# USB-PS2.net
KiCad netlist of a schematic drawn in EAGLE
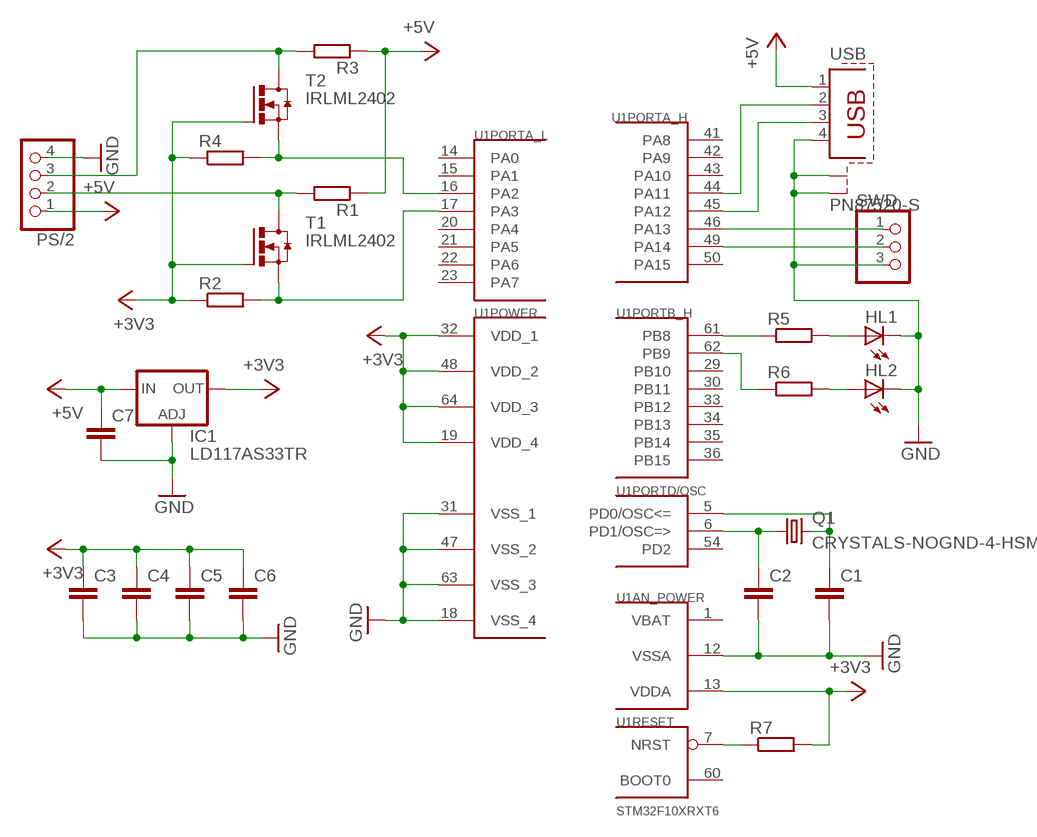
[diagram p0: schematic, sheet 1]

(export (version "E")
  (design (tool "Eeschema 10.0.6"))
  (components
    (comp (ref "C1")
      (value "C-EUC0603K")
      (footprint "eagle-import:C0603K")
      (libsource (lib "eagle-import") (part "C-EUC0603K"))
    )
    (comp (ref "C2")
      (value "C-EUC0603K")
      (footprint "eagle-import:C0603K")
      (libsource (lib "eagle-import") (part "C-EUC0603K"))
    )
    (comp (ref "C3")
      (value "C-EUC0603K")
      (footprint "eagle-import:C0603K")
      (libsource (lib "eagle-import") (part "C-EUC0603K"))
    )
    (comp (ref "C4")
      (value "C-EUC0603K")
      (footprint "eagle-import:C0603K")
      (libsource (lib "eagle-import") (part "C-EUC0603K"))
    )
    (comp (ref "C5")
      (value "C-EUC0603K")
      (footprint "eagle-import:C0603K")
      (libsource (lib "eagle-import") (part "C-EUC0603K"))
    )
    (comp (ref "C6")
      (value "C-EUC0603K")
      (footprint "eagle-import:C0603K")
      (libsource (lib "eagle-import") (part "C-EUC0603K"))
    )
    (comp (ref "C7")
      (value "C-EUC0603K")
      (footprint "eagle-import:C0603K")
      (libsource (lib "eagle-import") (part "C-EUC0603K"))
    )
    (comp (ref "HL1")
      (value "LEDSML0805")
      (footprint "eagle-import:SML0805")
      (libsource (lib "eagle-import") (part "LEDSML0805"))
    )
    (comp (ref "HL2")
      (value "LEDSML0805")
      (footprint "eagle-import:SML0805")
      (libsource (lib "eagle-import") (part "LEDSML0805"))
    )
    (comp (ref "IC1")
      (value "LD117AS33TR")
      (footprint "eagle-import:SOT223")
      (libsource (lib "eagle-import") (part "LD117A?S33TR"))
    )
    (comp (ref "PS/2")
      (value "PINHD-1X4")
      (footprint "eagle-import:1X04")
      (libsource (lib "eagle-import") (part "PINHD-1X4"))
    )
    (comp (ref "Q1")
      (value "CRYSTALS-NOGND-4-HSMX")
      (footprint "eagle-import:HC49-4-HSMX")
      (libsource (lib "eagle-import") (part "CRYSTALS-NOGND-4-HSMX"))
    )
    (comp (ref "R1")
      (value "R-EU_R0603")
      (footprint "eagle-import:R0603")
      (libsource (lib "eagle-import") (part "R-EU_R0603"))
    )
    (comp (ref "R2")
      (value "R-EU_R0603")
      (footprint "eagle-import:R0603")
      (libsource (lib "eagle-import") (part "R-EU_R0603"))
    )
    (comp (ref "R3")
      (value "R-EU_R0603")
      (footprint "eagle-import:R0603")
      (libsource (lib "eagle-import") (part "R-EU_R0603"))
    )
    (comp (ref "R4")
      (value "R-EU_R0603")
      (footprint "eagle-import:R0603")
      (libsource (lib "eagle-import") (part "R-EU_R0603"))
    )
    (comp (ref "R5")
      (value "R-EU_R0603")
      (footprint "eagle-import:R0603")
      (libsource (lib "eagle-import") (part "R-EU_R0603"))
    )
    (comp (ref "R6")
      (value "R-EU_R0603")
      (footprint "eagle-import:R0603")
      (libsource (lib "eagle-import") (part "R-EU_R0603"))
    )
    (comp (ref "R7")
      (value "R-EU_R0603")
      (footprint "eagle-import:R0603")
      (libsource (lib "eagle-import") (part "R-EU_R0603"))
    )
    (comp (ref "SWD")
      (value "PINHD-1X3")
      (footprint "eagle-import:1X03")
      (libsource (lib "eagle-import") (part "PINHD-1X3"))
    )
    (comp (ref "T1")
      (value "IRLML2402")
      (footprint "eagle-import:MICRO3")
      (libsource (lib "eagle-import") (part "IRLML2402"))
    )
    (comp (ref "T2")
      (value "IRLML2402")
      (footprint "eagle-import:MICRO3")
      (libsource (lib "eagle-import") (part "IRLML2402"))
    )
    (comp (ref "U1")
      (value "STM32F10XRXT6")
      (footprint "eagle-import:TQFP64")
      (libsource (lib "eagle-import") (part "STM32F10XRXT6"))
    )
    (comp (ref "USB")
      (value "PN87520-S")
      (footprint "eagle-import:PN87520-S")
      (libsource (lib "eagle-import") (part "PN87520-S"))
    )
  )
  (nets
    (net (code "1") (name "+3V3") (class "Default")
      (node (ref "C3") (pin "1") (pinfunction "1_1") (pintype "passive"))
      (node (ref "C4") (pin "1") (pinfunction "1_1") (pintype "passive"))
      (node (ref "C5") (pin "1") (pinfunction "1_1") (pintype "passive"))
      (node (ref "C6") (pin "1") (pinfunction "1_1") (pintype "passive"))
      (node (ref "IC1") (pin "4") (pinfunction "OUT_4") (pintype "passive"))
      (node (ref "R2") (pin "1") (pinfunction "1_1") (pintype "passive"))
      (node (ref "R4") (pin "1") (pinfunction "1_1") (pintype "passive"))
      (node (ref "R7") (pin "2") (pinfunction "2_2") (pintype "passive"))
      (node (ref "T1") (pin "1") (pinfunction "G_1") (pintype "passive"))
      (node (ref "T2") (pin "1") (pinfunction "G_1") (pintype "passive"))
      (node (ref "U1") (pin "13") (pinfunction "VDDA_13") (pintype "power_in"))
      (node (ref "U1") (pin "19") (pinfunction "VDD_4_19") (pintype "power_in"))
      (node (ref "U1") (pin "32") (pinfunction "VDD_1_32") (pintype "power_in"))
      (node (ref "U1") (pin "48") (pinfunction "VDD_2_48") (pintype "power_in"))
      (node (ref "U1") (pin "64") (pinfunction "VDD_3_64") (pintype "power_in"))
    )
    (net (code "2") (name "+5V") (class "Default")
      (node (ref "C7") (pin "1") (pinfunction "1_1") (pintype "passive"))
      (node (ref "IC1") (pin "3") (pinfunction "IN_3") (pintype "input"))
      (node (ref "PS/2") (pin "1") (pinfunction "1_1") (pintype "passive"))
      (node (ref "R1") (pin "1") (pinfunction "1_1") (pintype "passive"))
      (node (ref "R3") (pin "1") (pinfunction "1_1") (pintype "passive"))
      (node (ref "USB") (pin "1") (pinfunction "1_1") (pintype "passive"))
    )
    (net (code "3") (name "/VBAT") (class "Default")
      (node (ref "U1") (pin "1") (pinfunction "VBAT_1") (pintype "power_in"))
    )
    (net (code "4") (name "GND") (class "Default")
      (node (ref "C1") (pin "2") (pinfunction "2_2") (pintype "passive"))
      (node (ref "C2") (pin "2") (pinfunction "2_2") (pintype "passive"))
      (node (ref "C3") (pin "2") (pinfunction "2_2") (pintype "passive"))
      (node (ref "C4") (pin "2") (pinfunction "2_2") (pintype "passive"))
      (node (ref "C5") (pin "2") (pinfunction "2_2") (pintype "passive"))
      (node (ref "C6") (pin "2") (pinfunction "2_2") (pintype "passive"))
      (node (ref "C7") (pin "2") (pinfunction "2_2") (pintype "passive"))
      (node (ref "HL1") (pin "C") (pinfunction "C_C") (pintype "passive"))
      (node (ref "HL2") (pin "C") (pinfunction "C_C") (pintype "passive"))
      (node (ref "IC1") (pin "1") (pinfunction "ADJ_1") (pintype "input"))
      (node (ref "PS/2") (pin "4") (pinfunction "4_4") (pintype "passive"))
      (node (ref "SWD") (pin "3") (pinfunction "3_3") (pintype "passive"))
      (node (ref "U1") (pin "12") (pinfunction "VSSA_12") (pintype "power_in"))
      (node (ref "U1") (pin "18") (pinfunction "VSS_4_18") (pintype "power_in"))
      (node (ref "U1") (pin "31") (pinfunction "VSS_1_31") (pintype "power_in"))
      (node (ref "U1") (pin "47") (pinfunction "VSS_2_47") (pintype "power_in"))
      (node (ref "U1") (pin "63") (pinfunction "VSS_3_63") (pintype "power_in"))
      (node (ref "USB") (pin "4") (pinfunction "4_4") (pintype "passive"))
      (node (ref "USB") (pin "S1") (pinfunction "S1_S1") (pintype "passive"))
      (node (ref "USB") (pin "S2") (pinfunction "S2_S2") (pintype "passive"))
    )
    (net (code "5") (name "Net-(HL1-PadA)") (class "Default")
      (node (ref "HL1") (pin "A") (pinfunction "A_A") (pintype "passive"))
      (node (ref "R5") (pin "2") (pinfunction "2_2") (pintype "passive"))
    )
    (net (code "6") (name "Net-(HL2-PadA)") (class "Default")
      (node (ref "HL2") (pin "A") (pinfunction "A_A") (pintype "passive"))
      (node (ref "R6") (pin "2") (pinfunction "2_2") (pintype "passive"))
    )
    (net (code "7") (name "Net-(T1-D)") (class "Default")
      (node (ref "PS/2") (pin "2") (pinfunction "2_2") (pintype "passive"))
      (node (ref "R1") (pin "2") (pinfunction "2_2") (pintype "passive"))
      (node (ref "T1") (pin "3") (pinfunction "D_3") (pintype "passive"))
    )
    (net (code "8") (name "Net-(T1-S)") (class "Default")
      (node (ref "R2") (pin "2") (pinfunction "2_2") (pintype "passive"))
      (node (ref "T1") (pin "2") (pinfunction "S_2") (pintype "passive"))
      (node (ref "U1") (pin "17") (pinfunction "PA3_17") (pintype "bidirectional"))
    )
    (net (code "9") (name "Net-(T2-D)") (class "Default")
      (node (ref "PS/2") (pin "3") (pinfunction "3_3") (pintype "passive"))
      (node (ref "R3") (pin "2") (pinfunction "2_2") (pintype "passive"))
      (node (ref "T2") (pin "3") (pinfunction "D_3") (pintype "passive"))
    )
    (net (code "10") (name "Net-(T2-S)") (class "Default")
      (node (ref "R4") (pin "2") (pinfunction "2_2") (pintype "passive"))
      (node (ref "T2") (pin "2") (pinfunction "S_2") (pintype "passive"))
      (node (ref "U1") (pin "16") (pinfunction "PA2_16") (pintype "bidirectional"))
    )
    (net (code "11") (name "Net-(U1B-PA11)") (class "Default")
      (node (ref "U1") (pin "44") (pinfunction "PA11_44") (pintype "bidirectional"))
      (node (ref "USB") (pin "2") (pinfunction "2_2") (pintype "passive"))
    )
    (net (code "12") (name "Net-(U1B-PA12)") (class "Default")
      (node (ref "U1") (pin "45") (pinfunction "PA12_45") (pintype "bidirectional"))
      (node (ref "USB") (pin "3") (pinfunction "3_3") (pintype "passive"))
    )
    (net (code "13") (name "Net-(U1B-PA13)") (class "Default")
      (node (ref "SWD") (pin "1") (pinfunction "1_1") (pintype "passive"))
      (node (ref "U1") (pin "46") (pinfunction "PA13_46") (pintype "bidirectional"))
    )
    (net (code "14") (name "Net-(U1B-PA14)") (class "Default")
      (node (ref "SWD") (pin "2") (pinfunction "2_2") (pintype "passive"))
      (node (ref "U1") (pin "49") (pinfunction "PA14_49") (pintype "bidirectional"))
    )
    (net (code "15") (name "Net-(U1D-PB8)") (class "Default")
      (node (ref "R5") (pin "1") (pinfunction "1_1") (pintype "passive"))
      (node (ref "U1") (pin "61") (pinfunction "PB8_61") (pintype "bidirectional"))
    )
    (net (code "16") (name "Net-(U1D-PB9)") (class "Default")
      (node (ref "R6") (pin "1") (pinfunction "1_1") (pintype "passive"))
      (node (ref "U1") (pin "62") (pinfunction "PB9_62") (pintype "bidirectional"))
    )
    (net (code "17") (name "Net-(U1H-PD0{slash}OSC<=)") (class "Default")
      (node (ref "C1") (pin "1") (pinfunction "1_1") (pintype "passive"))
      (node (ref "Q1") (pin "2") (pinfunction "2_2") (pintype "passive"))
      (node (ref "U1") (pin "5") (pinfunction "PD0/OSC<=_5") (pintype "bidirectional"))
    )
    (net (code "18") (name "Net-(U1H-PD1{slash}OSC=>)") (class "Default")
      (node (ref "C2") (pin "1") (pinfunction "1_1") (pintype "passive"))
      (node (ref "Q1") (pin "1") (pinfunction "1_1") (pintype "passive"))
      (node (ref "U1") (pin "6") (pinfunction "PD1/OSC=>_6") (pintype "bidirectional"))
    )
    (net (code "19") (name "Net-(U1J-NRST)") (class "Default")
      (node (ref "R7") (pin "1") (pinfunction "1_1") (pintype "passive"))
      (node (ref "U1") (pin "7") (pinfunction "NRST_7") (pintype "input"))
    )
    (net (code "20") (name "unconnected-(U1B-PA8-Pad41)") (class "Default")
      (node (ref "U1") (pin "41") (pinfunction "PA8_41") (pintype "bidirectional"))
    )
    (net (code "21") (name "unconnected-(U1B-PA9-Pad42)") (class "Default")
      (node (ref "U1") (pin "42") (pinfunction "PA9_42") (pintype "bidirectional"))
    )
    (net (code "22") (name "unconnected-(U1B-PA10-Pad43)") (class "Default")
      (node (ref "U1") (pin "43") (pinfunction "PA10_43") (pintype "bidirectional"))
    )
    (net (code "23") (name "unconnected-(U1B-PA15-Pad50)") (class "Default")
      (node (ref "U1") (pin "50") (pinfunction "PA15_50") (pintype "bidirectional"))
    )
    (net (code "24") (name "unconnected-(U1C-PA0-Pad14)") (class "Default")
      (node (ref "U1") (pin "14") (pinfunction "PA0_14") (pintype "bidirectional"))
    )
    (net (code "25") (name "unconnected-(U1C-PA1-Pad15)") (class "Default")
      (node (ref "U1") (pin "15") (pinfunction "PA1_15") (pintype "bidirectional"))
    )
    (net (code "26") (name "unconnected-(U1C-PA4-Pad20)") (class "Default")
      (node (ref "U1") (pin "20") (pinfunction "PA4_20") (pintype "bidirectional"))
    )
    (net (code "27") (name "unconnected-(U1C-PA5-Pad21)") (class "Default")
      (node (ref "U1") (pin "21") (pinfunction "PA5_21") (pintype "bidirectional"))
    )
    (net (code "28") (name "unconnected-(U1C-PA6-Pad22)") (class "Default")
      (node (ref "U1") (pin "22") (pinfunction "PA6_22") (pintype "bidirectional"))
    )
    (net (code "29") (name "unconnected-(U1C-PA7-Pad23)") (class "Default")
      (node (ref "U1") (pin "23") (pinfunction "PA7_23") (pintype "bidirectional"))
    )
    (net (code "30") (name "unconnected-(U1D-PB10-Pad29)") (class "Default")
      (node (ref "U1") (pin "29") (pinfunction "PB10_29") (pintype "bidirectional"))
    )
    (net (code "31") (name "unconnected-(U1D-PB11-Pad30)") (class "Default")
      (node (ref "U1") (pin "30") (pinfunction "PB11_30") (pintype "bidirectional"))
    )
    (net (code "32") (name "unconnected-(U1D-PB12-Pad33)") (class "Default")
      (node (ref "U1") (pin "33") (pinfunction "PB12_33") (pintype "bidirectional"))
    )
    (net (code "33") (name "unconnected-(U1D-PB13-Pad34)") (class "Default")
      (node (ref "U1") (pin "34") (pinfunction "PB13_34") (pintype "bidirectional"))
    )
    (net (code "34") (name "unconnected-(U1D-PB14-Pad35)") (class "Default")
      (node (ref "U1") (pin "35") (pinfunction "PB14_35") (pintype "bidirectional"))
    )
    (net (code "35") (name "unconnected-(U1D-PB15-Pad36)") (class "Default")
      (node (ref "U1") (pin "36") (pinfunction "PB15_36") (pintype "bidirectional"))
    )
    (net (code "36") (name "unconnected-(U1H-PD2-Pad54)") (class "Default")
      (node (ref "U1") (pin "54") (pinfunction "PD2_54") (pintype "bidirectional"))
    )
    (net (code "37") (name "unconnected-(U1J-BOOT0-Pad60)") (class "Default")
      (node (ref "U1") (pin "60") (pinfunction "BOOT0_60") (pintype "input"))
    )
  )
)
